# ts2068Interface.net
KiCad netlist of a schematic drawn in Altium Designer
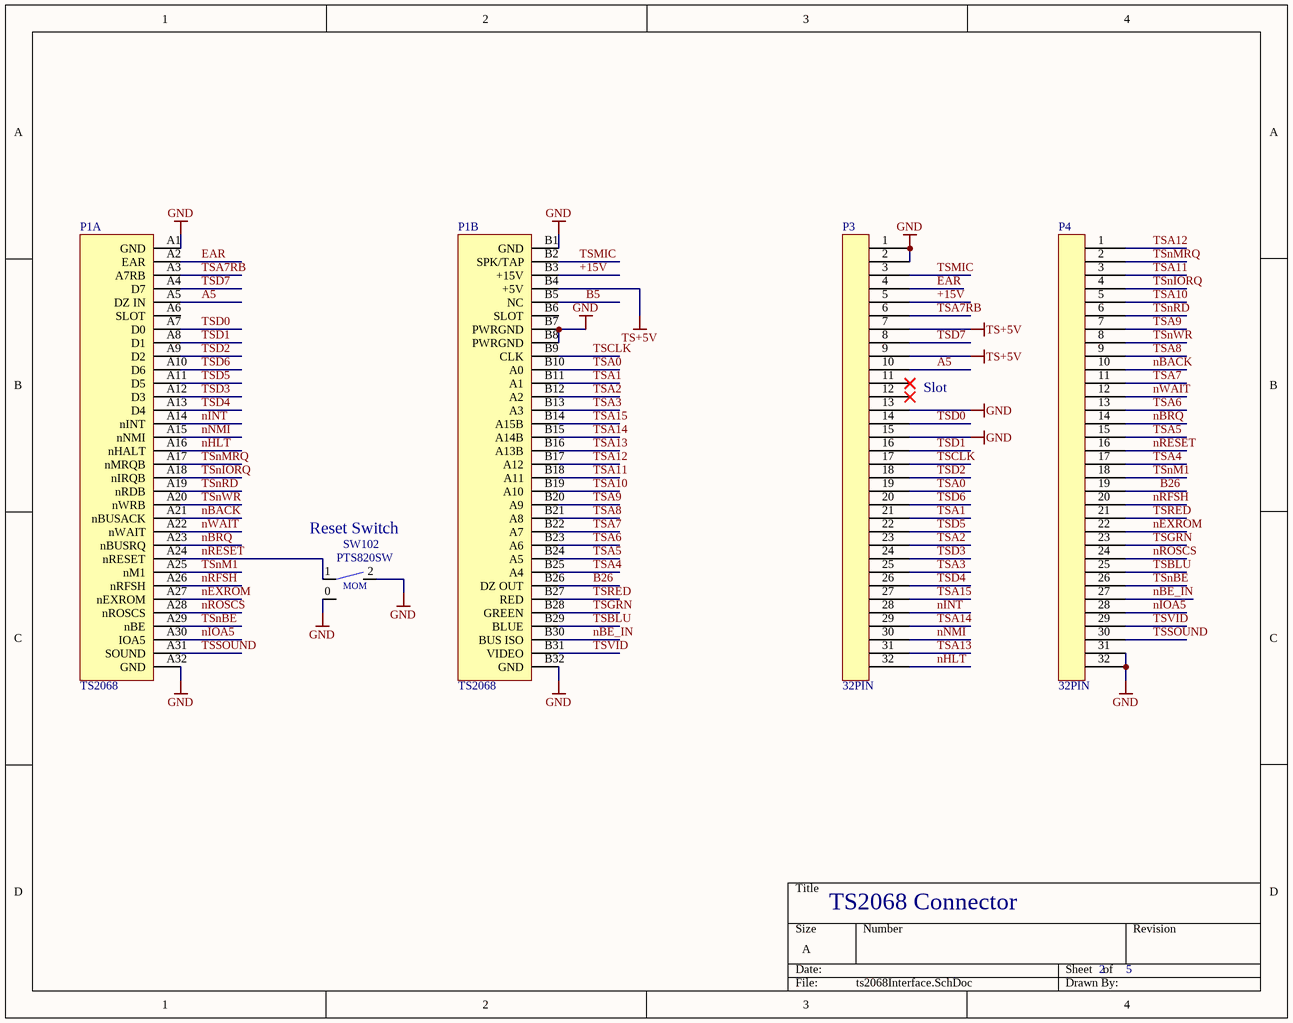
[diagram p0: ts2068Interface.SchDoc]

(export (version "E")
  (design (tool "Eeschema 10.0.6"))
  (components
    (comp (ref "P1") (value "TS2068") (footprint "TS2068A") (libsource (lib "Modules") (part "TS2068")))
    (comp (ref "P3") (value "32PIN") (footprint "IDC32") (libsource (lib "Connectors") (part "32PIN")))
    (comp (ref "P4") (value "32PIN") (footprint "IDC32") (libsource (lib "Connectors") (part "32PIN")))
    (comp (ref "SW102")
      (value "PTS820SW")
      (footprint "PTS820")
      (description "Tactile Switch SPST-NO Top Actuated Surface Mount")
      (fields (field (name "MFG") "C&K"))
      (libsource (lib "Misc") (part "PTS820SW"))
    )
  )
  (nets
    (net (code "1") (name "/+15V") (class "Default")
      (node (ref "P1") (pin "B3") (pinfunction "+15V_B3") (pintype "passive"))
      (node (ref "P3") (pin "5") (pintype "passive"))
    )
    (net (code "2") (name "/A5") (class "Default")
      (node (ref "P1") (pin "A5") (pinfunction "DZ_IN_A5") (pintype "passive"))
      (node (ref "P3") (pin "10") (pintype "passive"))
    )
    (net (code "3") (name "/B5") (class "Default")
      (node (ref "P1") (pin "B5") (pinfunction "NC_B5") (pintype "passive"))
    )
    (net (code "4") (name "/B26") (class "Default")
      (node (ref "P1") (pin "B26") (pinfunction "DZ_OUT_B26") (pintype "passive"))
      (node (ref "P4") (pin "19") (pintype "passive"))
    )
    (net (code "5") (name "/EAR") (class "Default")
      (node (ref "P1") (pin "A2") (pinfunction "EAR_A2") (pintype "passive"))
      (node (ref "P3") (pin "4") (pintype "passive"))
    )
    (net (code "6") (name "/TSA0") (class "Default")
      (node (ref "P1") (pin "B10") (pinfunction "A0_B10") (pintype "passive"))
      (node (ref "P3") (pin "19") (pintype "passive"))
    )
    (net (code "7") (name "/TSA1") (class "Default")
      (node (ref "P1") (pin "B11") (pinfunction "A1_B11") (pintype "passive"))
      (node (ref "P3") (pin "21") (pintype "passive"))
    )
    (net (code "8") (name "/TSA2") (class "Default")
      (node (ref "P1") (pin "B12") (pinfunction "A2_B12") (pintype "passive"))
      (node (ref "P3") (pin "23") (pintype "passive"))
    )
    (net (code "9") (name "/TSA3") (class "Default")
      (node (ref "P1") (pin "B13") (pinfunction "A3_B13") (pintype "passive"))
      (node (ref "P3") (pin "25") (pintype "passive"))
    )
    (net (code "10") (name "/TSA4") (class "Default")
      (node (ref "P1") (pin "B25") (pinfunction "A4_B25") (pintype "passive"))
      (node (ref "P4") (pin "17") (pintype "passive"))
    )
    (net (code "11") (name "/TSA5") (class "Default")
      (node (ref "P1") (pin "B24") (pinfunction "A5_B24") (pintype "passive"))
      (node (ref "P4") (pin "15") (pintype "passive"))
    )
    (net (code "12") (name "/TSA6") (class "Default")
      (node (ref "P1") (pin "B23") (pinfunction "A6_B23") (pintype "passive"))
      (node (ref "P4") (pin "13") (pintype "passive"))
    )
    (net (code "13") (name "/TSA7") (class "Default")
      (node (ref "P1") (pin "B22") (pinfunction "A7_B22") (pintype "passive"))
      (node (ref "P4") (pin "11") (pintype "passive"))
    )
    (net (code "14") (name "/TSA7RB") (class "Default")
      (node (ref "P1") (pin "A3") (pinfunction "A7RB_A3") (pintype "passive"))
      (node (ref "P3") (pin "6") (pintype "passive"))
    )
    (net (code "15") (name "/TSA8") (class "Default")
      (node (ref "P1") (pin "B21") (pinfunction "A8_B21") (pintype "passive"))
      (node (ref "P4") (pin "9") (pintype "passive"))
    )
    (net (code "16") (name "/TSA9") (class "Default")
      (node (ref "P1") (pin "B20") (pinfunction "A9_B20") (pintype "passive"))
      (node (ref "P4") (pin "7") (pintype "passive"))
    )
    (net (code "17") (name "/TSA10") (class "Default")
      (node (ref "P1") (pin "B19") (pinfunction "A10_B19") (pintype "passive"))
      (node (ref "P4") (pin "5") (pintype "passive"))
    )
    (net (code "18") (name "/TSA11") (class "Default")
      (node (ref "P1") (pin "B18") (pinfunction "A11_B18") (pintype "passive"))
      (node (ref "P4") (pin "3") (pintype "passive"))
    )
    (net (code "19") (name "/TSA12") (class "Default")
      (node (ref "P1") (pin "B17") (pinfunction "A12_B17") (pintype "passive"))
      (node (ref "P4") (pin "1") (pintype "passive"))
    )
    (net (code "20") (name "/TSA13") (class "Default")
      (node (ref "P1") (pin "B16") (pinfunction "A13B_B16") (pintype "passive"))
      (node (ref "P3") (pin "31") (pintype "passive"))
    )
    (net (code "21") (name "/TSA14") (class "Default")
      (node (ref "P1") (pin "B15") (pinfunction "A14B_B15") (pintype "passive"))
      (node (ref "P3") (pin "29") (pintype "passive"))
    )
    (net (code "22") (name "/TSA15") (class "Default")
      (node (ref "P1") (pin "B14") (pinfunction "A15B_B14") (pintype "passive"))
      (node (ref "P3") (pin "27") (pintype "passive"))
    )
    (net (code "23") (name "/TSBLU") (class "Default")
      (node (ref "P1") (pin "B29") (pinfunction "BLUE_B29") (pintype "passive"))
      (node (ref "P4") (pin "25") (pintype "passive"))
    )
    (net (code "24") (name "/TSCLK") (class "Default")
      (node (ref "P1") (pin "B9") (pinfunction "CLK_B9") (pintype "passive"))
      (node (ref "P3") (pin "17") (pintype "passive"))
    )
    (net (code "25") (name "/TSD0") (class "Default")
      (node (ref "P1") (pin "A7") (pinfunction "D0_A7") (pintype "passive"))
      (node (ref "P3") (pin "14") (pintype "passive"))
    )
    (net (code "26") (name "/TSD1") (class "Default")
      (node (ref "P1") (pin "A8") (pinfunction "D1_A8") (pintype "passive"))
      (node (ref "P3") (pin "16") (pintype "passive"))
    )
    (net (code "27") (name "/TSD2") (class "Default")
      (node (ref "P1") (pin "A9") (pinfunction "D2_A9") (pintype "passive"))
      (node (ref "P3") (pin "18") (pintype "passive"))
    )
    (net (code "28") (name "/TSD3") (class "Default")
      (node (ref "P1") (pin "A12") (pinfunction "D3_A12") (pintype "passive"))
      (node (ref "P3") (pin "24") (pintype "passive"))
    )
    (net (code "29") (name "/TSD4") (class "Default")
      (node (ref "P1") (pin "A13") (pinfunction "D4_A13") (pintype "passive"))
      (node (ref "P3") (pin "26") (pintype "passive"))
    )
    (net (code "30") (name "/TSD5") (class "Default")
      (node (ref "P1") (pin "A11") (pinfunction "D5_A11") (pintype "passive"))
      (node (ref "P3") (pin "22") (pintype "passive"))
    )
    (net (code "31") (name "/TSD6") (class "Default")
      (node (ref "P1") (pin "A10") (pinfunction "D6_A10") (pintype "passive"))
      (node (ref "P3") (pin "20") (pintype "passive"))
    )
    (net (code "32") (name "/TSD7") (class "Default")
      (node (ref "P1") (pin "A4") (pinfunction "D7_A4") (pintype "passive"))
      (node (ref "P3") (pin "8") (pintype "passive"))
    )
    (net (code "33") (name "/TSGRN") (class "Default")
      (node (ref "P1") (pin "B28") (pinfunction "GREEN_B28") (pintype "passive"))
      (node (ref "P4") (pin "23") (pintype "passive"))
    )
    (net (code "34") (name "/TSMIC") (class "Default")
      (node (ref "P1") (pin "B2") (pinfunction "SPK/TAP_B2") (pintype "passive"))
      (node (ref "P3") (pin "3") (pintype "passive"))
    )
    (net (code "35") (name "/TSRED") (class "Default")
      (node (ref "P1") (pin "B27") (pinfunction "RED_B27") (pintype "passive"))
      (node (ref "P4") (pin "21") (pintype "passive"))
    )
    (net (code "36") (name "/TSSOUND") (class "Default")
      (node (ref "P1") (pin "A31") (pinfunction "SOUND_A31") (pintype "passive"))
      (node (ref "P4") (pin "30") (pintype "passive"))
    )
    (net (code "37") (name "/TSVID") (class "Default")
      (node (ref "P1") (pin "B31") (pinfunction "VIDEO_B31") (pintype "passive"))
      (node (ref "P4") (pin "29") (pintype "passive"))
    )
    (net (code "38") (name "/TSnBE") (class "Default")
      (node (ref "P1") (pin "A29") (pinfunction "nBE_A29") (pintype "passive"))
      (node (ref "P4") (pin "26") (pintype "passive"))
    )
    (net (code "39") (name "/TSnIORQ") (class "Default")
      (node (ref "P1") (pin "A18") (pinfunction "nIRQB_A18") (pintype "passive"))
      (node (ref "P4") (pin "4") (pintype "passive"))
    )
    (net (code "40") (name "/TSnM1") (class "Default")
      (node (ref "P1") (pin "A25") (pinfunction "nM1_A25") (pintype "passive"))
      (node (ref "P4") (pin "18") (pintype "passive"))
    )
    (net (code "41") (name "/TSnMRQ") (class "Default")
      (node (ref "P1") (pin "A17") (pinfunction "nMRQB_A17") (pintype "passive"))
      (node (ref "P4") (pin "2") (pintype "passive"))
    )
    (net (code "42") (name "/TSnRD") (class "Default")
      (node (ref "P1") (pin "A19") (pinfunction "nRDB_A19") (pintype "passive"))
      (node (ref "P4") (pin "6") (pintype "passive"))
    )
    (net (code "43") (name "/TSnWR") (class "Default")
      (node (ref "P1") (pin "A20") (pinfunction "nWRB_A20") (pintype "passive"))
      (node (ref "P4") (pin "8") (pintype "passive"))
    )
    (net (code "44") (name "/nBACK") (class "Default")
      (node (ref "P1") (pin "A21") (pinfunction "nBUSACK_A21") (pintype "passive"))
      (node (ref "P4") (pin "10") (pintype "passive"))
    )
    (net (code "45") (name "/nBE_IN") (class "Default")
      (node (ref "P1") (pin "B30") (pinfunction "BUS_ISO_B30") (pintype "passive"))
      (node (ref "P4") (pin "27") (pintype "passive"))
    )
    (net (code "46") (name "/nBRQ") (class "Default")
      (node (ref "P1") (pin "A23") (pinfunction "nBUSRQ_A23") (pintype "passive"))
      (node (ref "P4") (pin "14") (pintype "passive"))
    )
    (net (code "47") (name "/nEXROM") (class "Default")
      (node (ref "P1") (pin "A27") (pinfunction "nEXROM_A27") (pintype "passive"))
      (node (ref "P4") (pin "22") (pintype "passive"))
    )
    (net (code "48") (name "/nHLT") (class "Default")
      (node (ref "P1") (pin "A16") (pinfunction "nHALT_A16") (pintype "passive"))
      (node (ref "P3") (pin "32") (pintype "passive"))
    )
    (net (code "49") (name "/nINT") (class "Default")
      (node (ref "P1") (pin "A14") (pinfunction "nINT_A14") (pintype "passive"))
      (node (ref "P3") (pin "28") (pintype "passive"))
    )
    (net (code "50") (name "/nIOA5") (class "Default")
      (node (ref "P1") (pin "A30") (pinfunction "IOA5_A30") (pintype "passive"))
      (node (ref "P4") (pin "28") (pintype "passive"))
    )
    (net (code "51") (name "/nNMI") (class "Default")
      (node (ref "P1") (pin "A15") (pinfunction "nNMI_A15") (pintype "passive"))
      (node (ref "P3") (pin "30") (pintype "passive"))
    )
    (net (code "52") (name "/nRESET") (class "Default")
      (node (ref "P1") (pin "A24") (pinfunction "nRESET_A24") (pintype "passive"))
      (node (ref "P4") (pin "16") (pintype "passive"))
      (node (ref "SW102") (pin "1") (pinfunction "1_1") (pintype "passive"))
    )
    (net (code "53") (name "/nRFSH") (class "Default")
      (node (ref "P1") (pin "A26") (pinfunction "nRFSH_A26") (pintype "passive"))
      (node (ref "P4") (pin "20") (pintype "passive"))
    )
    (net (code "54") (name "/nROSCS") (class "Default")
      (node (ref "P1") (pin "A28") (pinfunction "nROSCS_A28") (pintype "passive"))
      (node (ref "P4") (pin "24") (pintype "passive"))
    )
    (net (code "55") (name "/nWAIT") (class "Default")
      (node (ref "P1") (pin "A22") (pinfunction "nWAIT_A22") (pintype "passive"))
      (node (ref "P4") (pin "12") (pintype "passive"))
    )
    (net (code "56") (name "GND") (class "Default")
      (node (ref "P1") (pin "A1") (pinfunction "GND_A1") (pintype "passive"))
      (node (ref "P1") (pin "A32") (pinfunction "GND_A32") (pintype "passive"))
      (node (ref "P1") (pin "B1") (pinfunction "GND_B1") (pintype "passive"))
      (node (ref "P1") (pin "B32") (pinfunction "GND_B32") (pintype "passive"))
      (node (ref "P1") (pin "B7") (pinfunction "PWRGND_B7") (pintype "passive"))
      (node (ref "P1") (pin "B8") (pinfunction "PWRGND_B8") (pintype "passive"))
      (node (ref "P3") (pin "1") (pintype "passive"))
      (node (ref "P3") (pin "13") (pintype "passive"))
      (node (ref "P3") (pin "15") (pintype "passive"))
      (node (ref "P3") (pin "2") (pintype "passive"))
      (node (ref "P4") (pin "31") (pintype "passive"))
      (node (ref "P4") (pin "32") (pintype "passive"))
      (node (ref "SW102") (pin "0") (pinfunction "0_0") (pintype "passive"))
      (node (ref "SW102") (pin "2") (pinfunction "2_2") (pintype "passive"))
    )
    (net (code "57") (name "TS+5V") (class "Default")
      (node (ref "P1") (pin "B4") (pinfunction "+5V_B4") (pintype "passive"))
      (node (ref "P3") (pin "7") (pintype "passive"))
      (node (ref "P3") (pin "9") (pintype "passive"))
    )
    (net (code "58") (name "unconnected-(P1A-SLOT-PadA6)") (class "Default")
      (node (ref "P1") (pin "A6") (pinfunction "SLOT_A6") (pintype "passive"))
    )
    (net (code "59") (name "unconnected-(P1B-SLOT-PadB6)") (class "Default")
      (node (ref "P1") (pin "B6") (pinfunction "SLOT_B6") (pintype "passive"))
    )
    (net (code "60") (name "unconnected-(P3-Pad11)") (class "Default")
      (node (ref "P3") (pin "11") (pintype "passive+no_connect"))
    )
    (net (code "61") (name "unconnected-(P3-Pad12)") (class "Default")
      (node (ref "P3") (pin "12") (pintype "passive+no_connect"))
    )
  )
)
